# Loadcells.net
KiCad netlist of a schematic drawn in Altium Designer
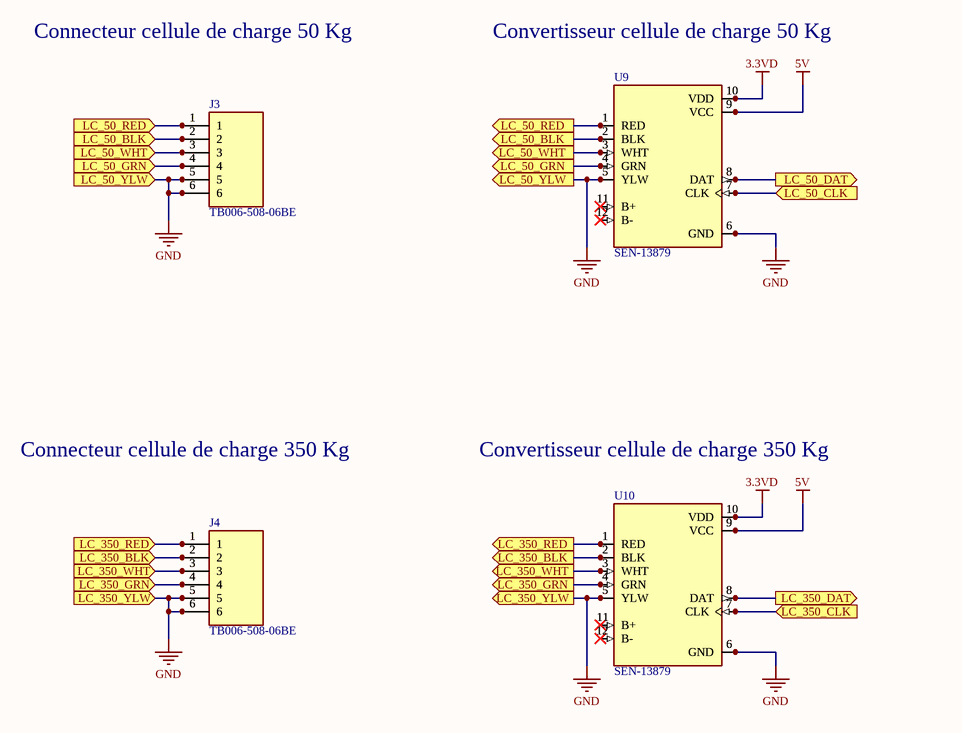
[diagram p0: Loadcells.SchDoc]

(export (version "E")
  (design (tool "Eeschema 10.0.6"))
  (components
    (comp (ref "J3")
      (value "TB006-508-06BE")
      (footprint "TB006-508-06BE")
      (description "TERMINAL BLOCK, SCREW TYPE, 5.08")
      (libsource (lib "TB006-508-06BE") (part "TB006-508-06BE"))
    )
    (comp (ref "J4")
      (value "TB006-508-06BE")
      (footprint "TB006-508-06BE")
      (description "TERMINAL BLOCK, SCREW TYPE, 5.08")
      (libsource (lib "TB006-508-06BE") (part "TB006-508-06BE"))
    )
    (comp (ref "U9")
      (value "SEN-13879")
      (footprint "SPARKFUN_SEN-13879")
      (description "External Input Sensor Amplifier")
      (fields (field (name "MF") "SparkFun"))
      (libsource (lib "SEN-13879") (part "SEN-13879"))
    )
    (comp (ref "U10")
      (value "SEN-13879")
      (footprint "SPARKFUN_SEN-13879")
      (description "External Input Sensor Amplifier")
      (fields (field (name "MF") "SparkFun"))
      (libsource (lib "SEN-13879") (part "SEN-13879"))
    )
  )
  (nets
    (net (code "1") (name "/LC_50_BLK") (class "Default")
      (node (ref "J3") (pin "2") (pinfunction "2_2") (pintype "passive"))
      (node (ref "U9") (pin "2") (pinfunction "BLK_2") (pintype "bidirectional"))
    )
    (net (code "2") (name "/LC_50_CLK") (class "Default")
      (node (ref "U9") (pin "7") (pinfunction "CLK_7") (pintype "input"))
    )
    (net (code "3") (name "/LC_50_DAT") (class "Default")
      (node (ref "U9") (pin "8") (pinfunction "DAT_8") (pintype "output"))
    )
    (net (code "4") (name "/LC_50_GRN") (class "Default")
      (node (ref "J3") (pin "4") (pinfunction "4_4") (pintype "passive"))
      (node (ref "U9") (pin "4") (pinfunction "GRN_4") (pintype "input"))
    )
    (net (code "5") (name "/LC_50_RED") (class "Default")
      (node (ref "J3") (pin "1") (pinfunction "1_1") (pintype "passive"))
      (node (ref "U9") (pin "1") (pinfunction "RED_1") (pintype "bidirectional"))
    )
    (net (code "6") (name "/LC_50_WHT") (class "Default")
      (node (ref "J3") (pin "3") (pinfunction "3_3") (pintype "passive"))
      (node (ref "U9") (pin "3") (pinfunction "WHT_3") (pintype "input"))
    )
    (net (code "7") (name "/LC_350_BLK") (class "Default")
      (node (ref "J4") (pin "2") (pinfunction "2_2") (pintype "passive"))
      (node (ref "U10") (pin "2") (pinfunction "BLK_2") (pintype "bidirectional"))
    )
    (net (code "8") (name "/LC_350_CLK") (class "Default")
      (node (ref "U10") (pin "7") (pinfunction "CLK_7") (pintype "input"))
    )
    (net (code "9") (name "/LC_350_DAT") (class "Default")
      (node (ref "U10") (pin "8") (pinfunction "DAT_8") (pintype "output"))
    )
    (net (code "10") (name "/LC_350_GRN") (class "Default")
      (node (ref "J4") (pin "4") (pinfunction "4_4") (pintype "passive"))
      (node (ref "U10") (pin "4") (pinfunction "GRN_4") (pintype "input"))
    )
    (net (code "11") (name "/LC_350_RED") (class "Default")
      (node (ref "J4") (pin "1") (pinfunction "1_1") (pintype "passive"))
      (node (ref "U10") (pin "1") (pinfunction "RED_1") (pintype "bidirectional"))
    )
    (net (code "12") (name "/LC_350_WHT") (class "Default")
      (node (ref "J4") (pin "3") (pinfunction "3_3") (pintype "passive"))
      (node (ref "U10") (pin "3") (pinfunction "WHT_3") (pintype "input"))
    )
    (net (code "13") (name "3.3VD") (class "Default")
      (node (ref "U10") (pin "10") (pinfunction "VDD_10") (pintype "power_in"))
      (node (ref "U9") (pin "10") (pinfunction "VDD_10") (pintype "power_in"))
    )
    (net (code "14") (name "5V") (class "Default")
      (node (ref "U10") (pin "9") (pinfunction "VCC_9") (pintype "power_in"))
      (node (ref "U9") (pin "9") (pinfunction "VCC_9") (pintype "power_in"))
    )
    (net (code "15") (name "GND") (class "Default")
      (node (ref "J3") (pin "5") (pinfunction "5_5") (pintype "passive"))
      (node (ref "J3") (pin "6") (pinfunction "6_6") (pintype "passive"))
      (node (ref "J4") (pin "5") (pinfunction "5_5") (pintype "passive"))
      (node (ref "J4") (pin "6") (pinfunction "6_6") (pintype "passive"))
      (node (ref "U10") (pin "5") (pinfunction "YLW_5") (pintype "bidirectional"))
      (node (ref "U10") (pin "6") (pinfunction "GND_6") (pintype "power_in"))
      (node (ref "U9") (pin "5") (pinfunction "YLW_5") (pintype "bidirectional"))
      (node (ref "U9") (pin "6") (pinfunction "GND_6") (pintype "power_in"))
    )
    (net (code "16") (name "unconnected-(U9-B+-Pad11)") (class "Default")
      (node (ref "U9") (pin "11") (pinfunction "B+_11") (pintype "input+no_connect"))
    )
    (net (code "17") (name "unconnected-(U9-B--Pad12)") (class "Default")
      (node (ref "U9") (pin "12") (pinfunction "B-_12") (pintype "input+no_connect"))
    )
    (net (code "18") (name "unconnected-(U10-B+-Pad11)") (class "Default")
      (node (ref "U10") (pin "11") (pinfunction "B+_11") (pintype "input+no_connect"))
    )
    (net (code "19") (name "unconnected-(U10-B--Pad12)") (class "Default")
      (node (ref "U10") (pin "12") (pinfunction "B-_12") (pintype "input+no_connect"))
    )
  )
)
